# eFuse.net
KiCad netlist of a schematic drawn in Altium Designer
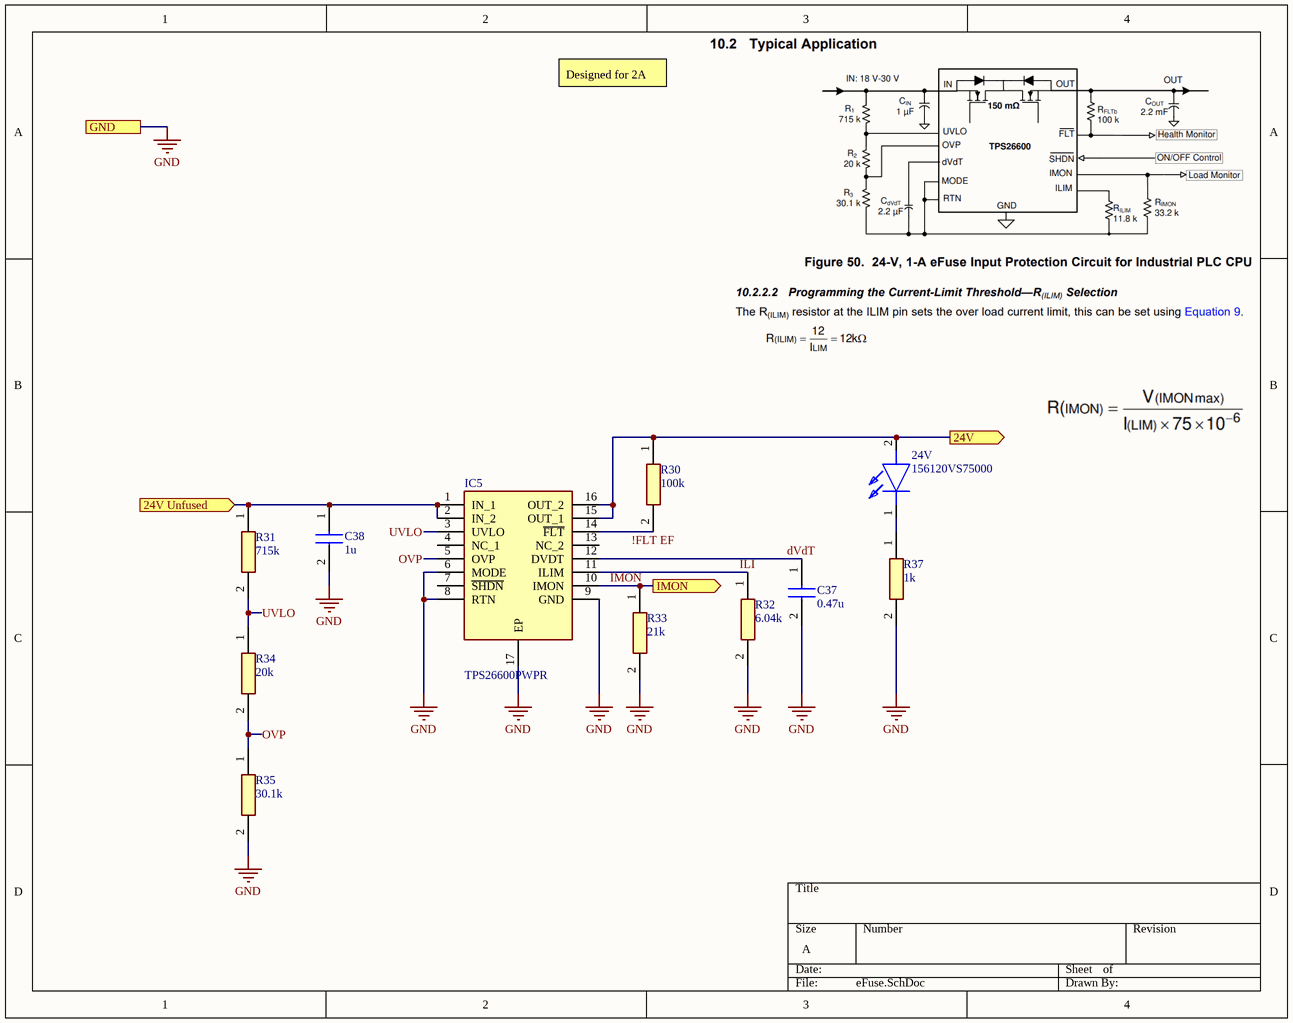
[diagram p0: eFuse.SchDoc]

(export (version "E")
  (design (tool "Eeschema 10.0.6"))
  (components
    (comp (ref "24V")
      (value "156120VS75000")
      (footprint "SamacSys:156120VS75000")
      (description "LED")
      (fields (field (name "MOUSER PART NUMBER") "710-156120VS75000"))
      (libsource (lib "SamacSys") (part "156120VS75000"))
    )
    (comp (ref "C37")
      (value "0.47u")
      (footprint "SamacSys:CAPC3216X152N")
      (description "Capacitor")
      (fields
        (field (name "MANUFACTURER_PART_NUMBER") "KAF31ER71H474KL")
        (field (name "MOUSER PART NUMBER") "581-KAF31ER71H474KL")
      )
      (libsource (lib "*") (part "KAF31ER71H474KL"))
    )
    (comp (ref "C38")
      (value "1u")
      (footprint "SamacSys:CAPC3216X178N")
      (description "Capacitor")
      (fields
        (field (name "MANUFACTURER_PART_NUMBER") "KGF31GR72A105KU")
        (field (name "MOUSER PART NUMBER") "581-KGF31GR72A105KU")
      )
      (libsource (lib "*") (part "KGF31GR72A105KU"))
    )
    (comp (ref "IC5")
      (value "TPS26600PWPR")
      (footprint "SamacSys:SOP65P640X120-17N")
      (description "Integrated Circuit")
      (fields (field (name "MOUSER PART NUMBER") "595-TPS26600PWPR"))
      (libsource (lib "*") (part "TPS26600PWPR"))
    )
    (comp (ref "R30")
      (value "100k")
      (footprint "SamacSys:RESC3216X65N")
      (description "Resistor")
      (fields (field (name "MANUFACTURER_PART_NUMBER") "MCA1206ME1003BP500"))
      (libsource (lib "*") (part "MCA1206ME1003BP500"))
    )
    (comp (ref "R31")
      (value "715k")
      (footprint "SamacSys:RESC3216X70N")
      (description "Resistor")
      (fields
        (field (name "MANUFACTURER_PART_NUMBER") "ERA-8AEB7153V")
        (field (name "MOUSER PART NUMBER") "667-ERA-8AEB7153V")
      )
      (libsource (lib "*") (part "ERA-8AEB7153V"))
    )
    (comp (ref "R32")
      (value "6.04k")
      (footprint "SamacSys:RESC3216X70N")
      (description "Resistor")
      (fields (field (name "MANUFACTURER_PART_NUMBER") "ERA-8AEB6041V"))
      (libsource (lib "*") (part "ERA-8AEB6041V"))
    )
    (comp (ref "R33")
      (value "21k")
      (footprint "SamacSys:RESC3216X70N")
      (description "Resistor")
      (fields
        (field (name "MANUFACTURER_PART_NUMBER") "ERA-8AEB2102V")
        (field (name "MOUSER PART NUMBER") "667-ERA-8AEB2102V")
      )
      (libsource (lib "*") (part "ERA-8AEB2102V"))
    )
    (comp (ref "R34")
      (value "20k")
      (footprint "SamacSys:RESC3216X70N")
      (description "Resistor")
      (fields
        (field (name "MANUFACTURER_PART_NUMBER") "ERA-8ARB203V")
        (field (name "MOUSER PART NUMBER") "667-ERA-8ARB203V")
      )
      (libsource (lib "*") (part "ERA-8ARB203V"))
    )
    (comp (ref "R35")
      (value "30.1k")
      (footprint "SamacSys:RESC3216X70N")
      (description "Resistor")
      (fields
        (field (name "MANUFACTURER_PART_NUMBER") "ERA-8AEB3012V")
        (field (name "MOUSER PART NUMBER") "667-ERA-8AEB3012V")
      )
      (libsource (lib "*") (part "ERA-8AEB3012V"))
    )
    (comp (ref "R37")
      (value "1k")
      (footprint "SamacSys:RESC3116X65N")
      (description "Resistor")
      (fields
        (field (name "MANUFACTURER_PART_NUMBER") "CRGS1206J1K0")
        (field (name "MOUSER PART NUMBER") "279-CRGS1206J1K0")
      )
      (libsource (lib "*") (part "CRGS1206J1K0"))
    )
  )
  (nets
    (net (code "1") (name "/!FLT EF") (class "Default")
      (node (ref "IC5") (pin "14") (pinfunction "~{FLT}_14") (pintype "passive"))
      (node (ref "R30") (pin "2") (pinfunction "2_2") (pintype "passive"))
    )
    (net (code "2") (name "/24V") (class "Default")
      (node (ref "24V") (pin "2") (pinfunction "A_2") (pintype "passive"))
      (node (ref "IC5") (pin "15") (pinfunction "OUT_1_15") (pintype "passive"))
      (node (ref "IC5") (pin "16") (pinfunction "OUT_2_16") (pintype "passive"))
      (node (ref "R30") (pin "1") (pinfunction "1_1") (pintype "passive"))
    )
    (net (code "3") (name "/24V Unfused") (class "Default")
      (node (ref "C38") (pin "1") (pinfunction "1_1") (pintype "passive"))
      (node (ref "IC5") (pin "1") (pinfunction "IN_1_1") (pintype "passive"))
      (node (ref "IC5") (pin "2") (pinfunction "IN_2_2") (pintype "passive"))
      (node (ref "R31") (pin "1") (pinfunction "1_1") (pintype "passive"))
    )
    (net (code "4") (name "/ILI") (class "Default")
      (node (ref "IC5") (pin "11") (pinfunction "ILIM_11") (pintype "passive"))
      (node (ref "R32") (pin "1") (pinfunction "1_1") (pintype "passive"))
    )
    (net (code "5") (name "/IMON") (class "Default")
      (node (ref "IC5") (pin "10") (pinfunction "IMON_10") (pintype "passive"))
      (node (ref "R33") (pin "1") (pinfunction "1_1") (pintype "passive"))
    )
    (net (code "6") (name "/OVP") (class "Default")
      (node (ref "IC5") (pin "5") (pinfunction "OVP_5") (pintype "passive"))
      (node (ref "R34") (pin "2") (pinfunction "2_2") (pintype "passive"))
      (node (ref "R35") (pin "1") (pinfunction "1_1") (pintype "passive"))
    )
    (net (code "7") (name "/UVLO") (class "Default")
      (node (ref "IC5") (pin "3") (pinfunction "UVLO_3") (pintype "passive"))
      (node (ref "R31") (pin "2") (pinfunction "2_2") (pintype "passive"))
      (node (ref "R34") (pin "1") (pinfunction "1_1") (pintype "passive"))
    )
    (net (code "8") (name "/dVdT") (class "Default")
      (node (ref "C37") (pin "1") (pinfunction "1_1") (pintype "passive"))
      (node (ref "IC5") (pin "12") (pinfunction "DVDT_12") (pintype "passive"))
    )
    (net (code "9") (name "GND") (class "Default")
      (node (ref "C37") (pin "2") (pinfunction "2_2") (pintype "passive"))
      (node (ref "C38") (pin "2") (pinfunction "2_2") (pintype "passive"))
      (node (ref "IC5") (pin "17") (pinfunction "EP_17") (pintype "passive"))
      (node (ref "IC5") (pin "6") (pinfunction "MODE_6") (pintype "passive"))
      (node (ref "IC5") (pin "8") (pinfunction "RTN_8") (pintype "passive"))
      (node (ref "IC5") (pin "9") (pinfunction "GND_9") (pintype "passive"))
      (node (ref "R32") (pin "2") (pinfunction "2_2") (pintype "passive"))
      (node (ref "R33") (pin "2") (pinfunction "2_2") (pintype "passive"))
      (node (ref "R35") (pin "2") (pinfunction "2_2") (pintype "passive"))
      (node (ref "R37") (pin "2") (pinfunction "2_2") (pintype "passive"))
    )
    (net (code "10") (name "Net-(24V-K)") (class "Default")
      (node (ref "24V") (pin "1") (pinfunction "K_1") (pintype "passive"))
      (node (ref "R37") (pin "1") (pinfunction "1_1") (pintype "passive"))
    )
    (net (code "11") (name "unconnected-(IC5-NC_1-Pad4)") (class "Default")
      (node (ref "IC5") (pin "4") (pinfunction "NC_1_4") (pintype "passive"))
    )
    (net (code "12") (name "unconnected-(IC5-NC_2-Pad13)") (class "Default")
      (node (ref "IC5") (pin "13") (pinfunction "NC_2_13") (pintype "passive"))
    )
    (net (code "13") (name "unconnected-(IC5-~{SHDN}-Pad7)") (class "Default")
      (node (ref "IC5") (pin "7") (pinfunction "~{SHDN}_7") (pintype "passive"))
    )
  )
)
